# CAN_Connections.net
KiCad netlist of a schematic drawn in Altium Designer
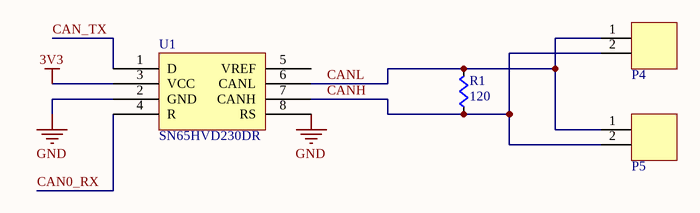
[diagram p0: CAN_Connections.SchDoc]

(export (version "E")
  (design (tool "Eeschema 10.0.6"))
  (components
    (comp (ref "P4")
      (value "2-pin Horz Sherlock")
      (footprint "MOLEX-HDR-1X2-SHERLOCK-HORZ")
      (fields
        (field (name "MANUFACTURER PART NUMBER") "0353630260")
        (field (name "MANUFACTURER") "Molex Inc")
      )
      (libsource (lib "SubjuGator8") (part "MOLEX-HDR-1x2-SHERLOCK_RA"))
    )
    (comp (ref "P5")
      (value "2-pin Horz Sherlock")
      (footprint "MOLEX-HDR-1X2-SHERLOCK-HORZ")
      (fields
        (field (name "MANUFACTURER PART NUMBER") "0353630260")
        (field (name "MANUFACTURER") "Molex Inc")
      )
      (libsource (lib "SubjuGator8") (part "MOLEX-HDR-1x2-SHERLOCK_RA"))
    )
    (comp (ref "R1")
      (value "120")
      (footprint "RES0603")
      (fields (field (name "Comment") "Res"))
      (libsource (lib "SubjuGator8") (part "Res"))
    )
    (comp (ref "U1")
      (value "SN65HVD230DR")
      (footprint "SOIC-8pin")
      (description "IC TXRX CAN 1MBPS 3.3V 8SOIC")
      (libsource (lib "SubjuGator8") (part "SN65HVD230DR"))
    )
  )
  (nets
    (net (code "1") (name "/CAN0_RX") (class "Default")
      (node (ref "U1") (pin "4") (pinfunction "R_4") (pintype "passive"))
    )
    (net (code "2") (name "/CANH") (class "Default")
      (node (ref "P4") (pin "2") (pinfunction "2_2") (pintype "passive"))
      (node (ref "P5") (pin "2") (pinfunction "2_2") (pintype "passive"))
      (node (ref "R1") (pin "2") (pinfunction "B_2") (pintype "passive"))
      (node (ref "U1") (pin "7") (pinfunction "CANH_7") (pintype "passive"))
    )
    (net (code "3") (name "/CANL") (class "Default")
      (node (ref "P4") (pin "1") (pinfunction "1_1") (pintype "passive"))
      (node (ref "P5") (pin "1") (pinfunction "1_1") (pintype "passive"))
      (node (ref "R1") (pin "1") (pinfunction "A_1") (pintype "passive"))
      (node (ref "U1") (pin "6") (pinfunction "CANL_6") (pintype "passive"))
    )
    (net (code "4") (name "/CAN_TX") (class "Default")
      (node (ref "U1") (pin "1") (pinfunction "D_1") (pintype "passive"))
    )
    (net (code "5") (name "3V3") (class "Default")
      (node (ref "U1") (pin "3") (pinfunction "VCC_3") (pintype "passive"))
    )
    (net (code "6") (name "GND") (class "Default")
      (node (ref "U1") (pin "2") (pinfunction "GND_2") (pintype "passive"))
      (node (ref "U1") (pin "8") (pinfunction "RS_8") (pintype "passive"))
    )
    (net (code "7") (name "unconnected-(U1-VREF-Pad5)") (class "Default")
      (node (ref "U1") (pin "5") (pinfunction "VREF_5") (pintype "passive"))
    )
  )
)
